# match2.net
KiCad netlist of a schematic drawn in EAGLE
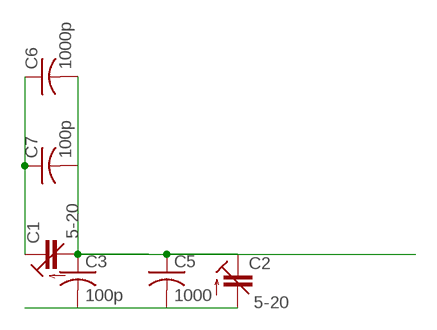
[diagram p0: schematic, sheet 1]

(export (version "E")
  (design (tool "Eeschema 10.0.6"))
  (components
    (comp (ref "C1")
      (value "5-20")
      (footprint "eagle-import:SGC3S")
      (libsource (lib "eagle-import") (part "C-TRIMM"))
    )
    (comp (ref "C2")
      (value "5-20")
      (footprint "eagle-import:SGC3S")
      (libsource (lib "eagle-import") (part "C-TRIMM"))
    )
    (comp (ref "C3")
      (value "100p")
      (footprint "eagle-import:C0603")
      (libsource (lib "eagle-import") (part "C-USC0603"))
    )
    (comp (ref "C5")
      (value "1000")
      (footprint "eagle-import:C0805")
      (libsource (lib "eagle-import") (part "C-USC0805"))
    )
    (comp (ref "C6")
      (value "1000p")
      (footprint "eagle-import:C0805")
      (libsource (lib "eagle-import") (part "C-USC0805"))
    )
    (comp (ref "C7")
      (value "100p")
      (footprint "eagle-import:C0603")
      (libsource (lib "eagle-import") (part "C-USC0603"))
    )
  )
  (nets
    (net (code "1") (name "Net-(C1-A)") (class "Default")
      (node (ref "C1") (pin "P$1") (pinfunction "A_P$1") (pintype "passive"))
      (node (ref "C2") (pin "P$2") (pinfunction "E_P$2") (pintype "passive"))
      (node (ref "C3") (pin "1") (pinfunction "1_1") (pintype "passive"))
      (node (ref "C5") (pin "1") (pinfunction "1_1") (pintype "passive"))
      (node (ref "C6") (pin "2") (pinfunction "2_2") (pintype "passive"))
      (node (ref "C7") (pin "2") (pinfunction "2_2") (pintype "passive"))
    )
    (net (code "2") (name "Net-(C1-E)") (class "Default")
      (node (ref "C1") (pin "P$2") (pinfunction "E_P$2") (pintype "passive"))
      (node (ref "C6") (pin "1") (pinfunction "1_1") (pintype "passive"))
      (node (ref "C7") (pin "1") (pinfunction "1_1") (pintype "passive"))
    )
    (net (code "3") (name "Net-(C2-A)") (class "Default")
      (node (ref "C2") (pin "P$1") (pinfunction "A_P$1") (pintype "passive"))
      (node (ref "C3") (pin "2") (pinfunction "2_2") (pintype "passive"))
      (node (ref "C5") (pin "2") (pinfunction "2_2") (pintype "passive"))
    )
  )
)
